# design.net
KiCad netlist of a schematic drawn in Altium Designer
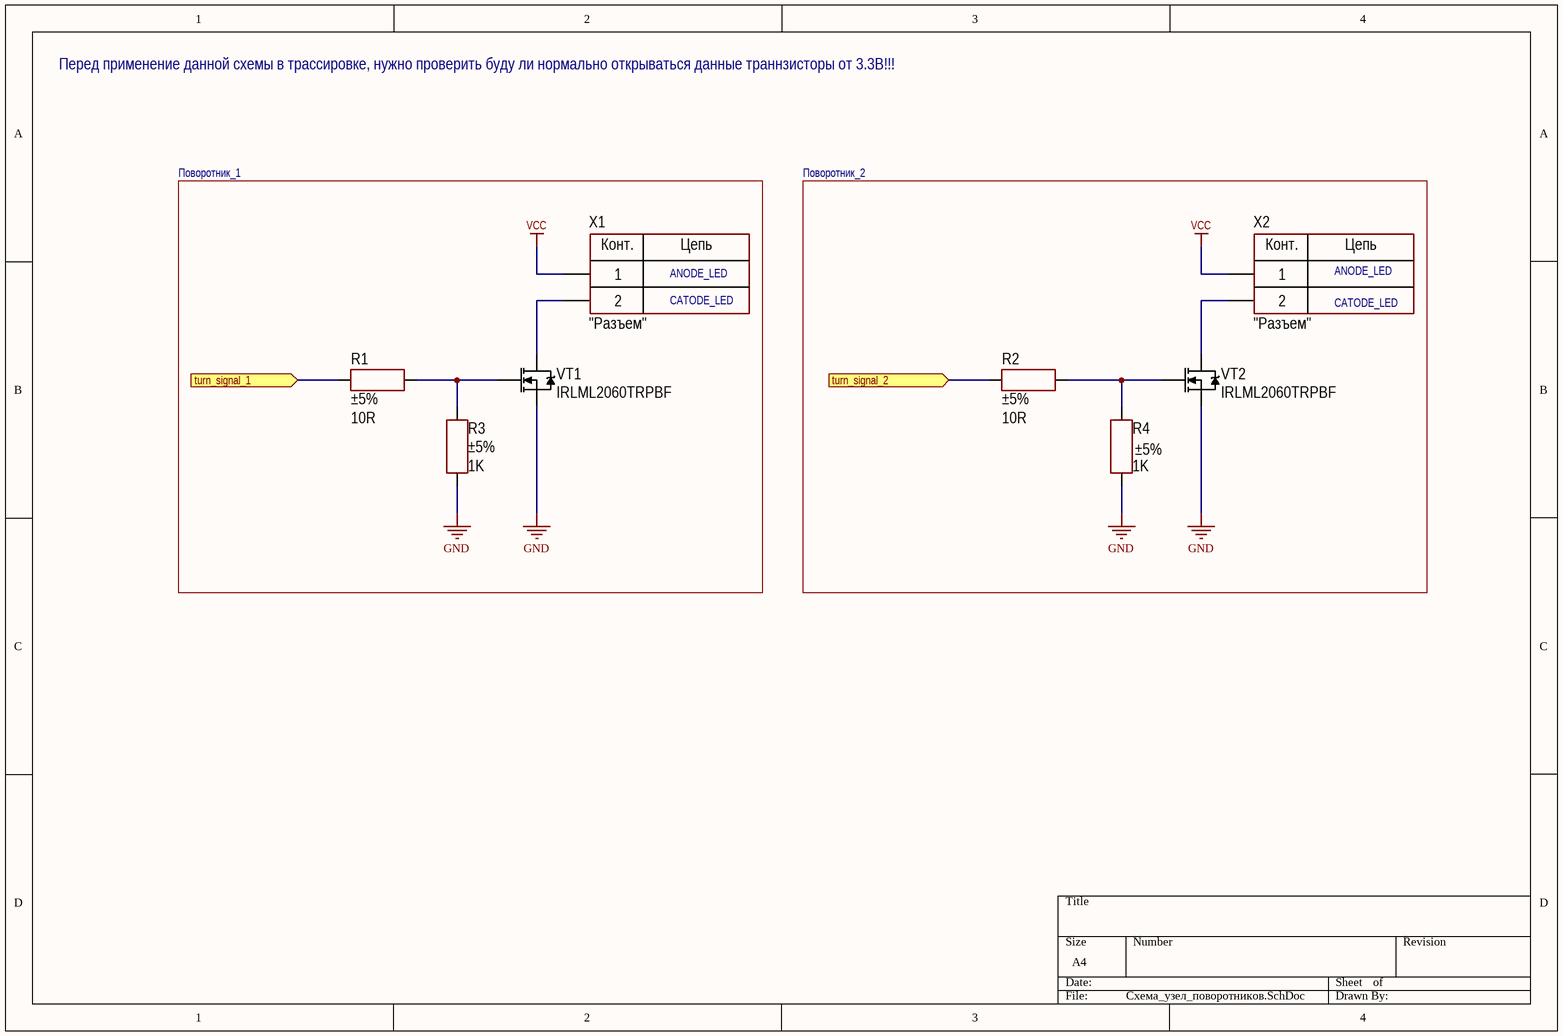
[diagram p0: Схема_узел_поворотников.SchDoc]

(export (version "E")
  (design (tool "Eeschema 10.0.6"))
  (components
    (comp (ref "R1")
      (value "10R")
      (footprint "RES: 0603")
      (fields
        (field (name "MANUFACTURER") "Yageo")
        (field (name "PARTNUMBER") "RC0603JR-07100RL")
        (field (name "VALUEMANUFACTURERPARTNUMBER") "Resistor film, 10R, ±5%, 0603, 0.1W, -55...+125°C")
        (field (name "TOLERANCE") "±5%")
      )
      (libsource (lib "resistor") (part "Resistor_0603"))
    )
    (comp (ref "R2")
      (value "10R")
      (footprint "RES: 0603")
      (fields
        (field (name "MANUFACTURER") "Yageo")
        (field (name "PARTNUMBER") "RC0603JR-07100RL")
        (field (name "VALUEMANUFACTURERPARTNUMBER") "Resistor film, 10R, ±5%, 0603, 0.1W, -55...+125°C")
        (field (name "TOLERANCE") "±5%")
      )
      (libsource (lib "resistor") (part "Resistor_0603"))
    )
    (comp (ref "R3")
      (value "1K")
      (footprint "RES: 0603")
      (fields
        (field (name "MANUFACTURER") "Yageo")
        (field (name "PARTNUMBER") "RC0603JR-07100RL")
        (field (name "VALUEMANUFACTURERPARTNUMBER") "Resistor film, 1K, ±5%, 0603, 0.1W, -55...+125°C")
        (field (name "TOLERANCE") "±5%")
      )
      (libsource (lib "") (part "Resistor_0603_1"))
    )
    (comp (ref "R4")
      (value "1K")
      (footprint "RES: 0603")
      (fields
        (field (name "MANUFACTURER") "Yageo")
        (field (name "PARTNUMBER") "RC0603JR-07100RL")
        (field (name "VALUEMANUFACTURERPARTNUMBER") "Resistor film, 1K, ±5%, 0603, 0.1W, -55...+125°C")
        (field (name "TOLERANCE") "±5%")
      )
      (libsource (lib "") (part "Resistor_0603_1"))
    )
    (comp (ref "VT1")
      (value "~")
      (footprint "SOT23")
      (fields
        (field (name "MANUFACTURER") "Infineon Technologies")
        (field (name "VALUEMANUFACTURERPARTNUMBER") "MOSFET N-channel transistor, 80V, 7A, 9.1nC, 2.5W, 34mOhm, 756pF, 8-TDSON, -55...+150°C")
        (field (name "PARTNUMBER") "IRLML2060TRPBF")
      )
      (libsource (lib "transistor") (part "MOSFET_N_132"))
    )
    (comp (ref "VT2")
      (value "~")
      (footprint "SOT23")
      (fields
        (field (name "MANUFACTURER") "Infineon Technologies")
        (field (name "VALUEMANUFACTURERPARTNUMBER") "MOSFET N-channel transistor, 80V, 7A, 9.1nC, 2.5W, 34mOhm, 756pF, 8-TDSON, -55...+150°C")
        (field (name "PARTNUMBER") "IRLML2060TRPBF")
      )
      (libsource (lib "transistor") (part "MOSFET_N_132"))
    )
    (comp (ref "X1")
      (value "~")
      (footprint "CON: DG350-3.5-02P")
      (fields
        (field (name "MANUFACTURER") "Degson")
        (field (name "VALUEMANUFACTURERPARTNUMBER") "Terminal connector, 2pin, 3.5mm, 300VAC, 10A")
        (field (name "PARTNUMBER") "DG350-3.5-02P-14")
        (field (name "COMMENTTEXT") "\"Разъем\"")
      )
      (libsource (lib "connector") (part "Connector_terminal_2pin"))
    )
    (comp (ref "X2")
      (value "~")
      (footprint "CON: DG350-3.5-02P")
      (fields
        (field (name "MANUFACTURER") "Degson")
        (field (name "VALUEMANUFACTURERPARTNUMBER") "Terminal connector, 2pin, 3.5mm, 300VAC, 10A")
        (field (name "PARTNUMBER") "DG350-3.5-02P-14")
        (field (name "COMMENTTEXT") "\"Разъем\"")
      )
      (libsource (lib "connector") (part "Connector_terminal_2pin"))
    )
  )
  (nets
    (net (code "1") (name "/turn_signal_1") (class "Default")
      (node (ref "R1") (pin "1") (pinfunction "1_1") (pintype "passive"))
    )
    (net (code "2") (name "/turn_signal_2") (class "Default")
      (node (ref "R2") (pin "1") (pinfunction "1_1") (pintype "passive"))
    )
    (net (code "3") (name "GND") (class "Default")
      (node (ref "R3") (pin "1") (pinfunction "1_1") (pintype "passive"))
      (node (ref "R4") (pin "1") (pinfunction "1_1") (pintype "passive"))
      (node (ref "VT1") (pin "2") (pinfunction "S_2") (pintype "passive"))
      (node (ref "VT2") (pin "2") (pinfunction "S_2") (pintype "passive"))
    )
    (net (code "4") (name "Net-(VT1-D)") (class "Default")
      (node (ref "VT1") (pin "3") (pinfunction "D_3") (pintype "passive"))
      (node (ref "X1") (pin "2") (pinfunction "2_2") (pintype "passive"))
    )
    (net (code "5") (name "Net-(VT1-G)") (class "Default")
      (node (ref "R1") (pin "2") (pinfunction "2_2") (pintype "passive"))
      (node (ref "R3") (pin "2") (pinfunction "2_2") (pintype "passive"))
      (node (ref "VT1") (pin "1") (pinfunction "G_1") (pintype "passive"))
    )
    (net (code "6") (name "Net-(VT2-D)") (class "Default")
      (node (ref "VT2") (pin "3") (pinfunction "D_3") (pintype "passive"))
      (node (ref "X2") (pin "2") (pinfunction "2_2") (pintype "passive"))
    )
    (net (code "7") (name "Net-(VT2-G)") (class "Default")
      (node (ref "R2") (pin "2") (pinfunction "2_2") (pintype "passive"))
      (node (ref "R4") (pin "2") (pinfunction "2_2") (pintype "passive"))
      (node (ref "VT2") (pin "1") (pinfunction "G_1") (pintype "passive"))
    )
    (net (code "8") (name "VCC") (class "Default")
      (node (ref "X1") (pin "1") (pinfunction "1_1") (pintype "passive"))
      (node (ref "X2") (pin "1") (pinfunction "1_1") (pintype "passive"))
    )
  )
)
